# Adafruit_NeoMatrix_8x8.net
KiCad netlist of a schematic drawn in EAGLE
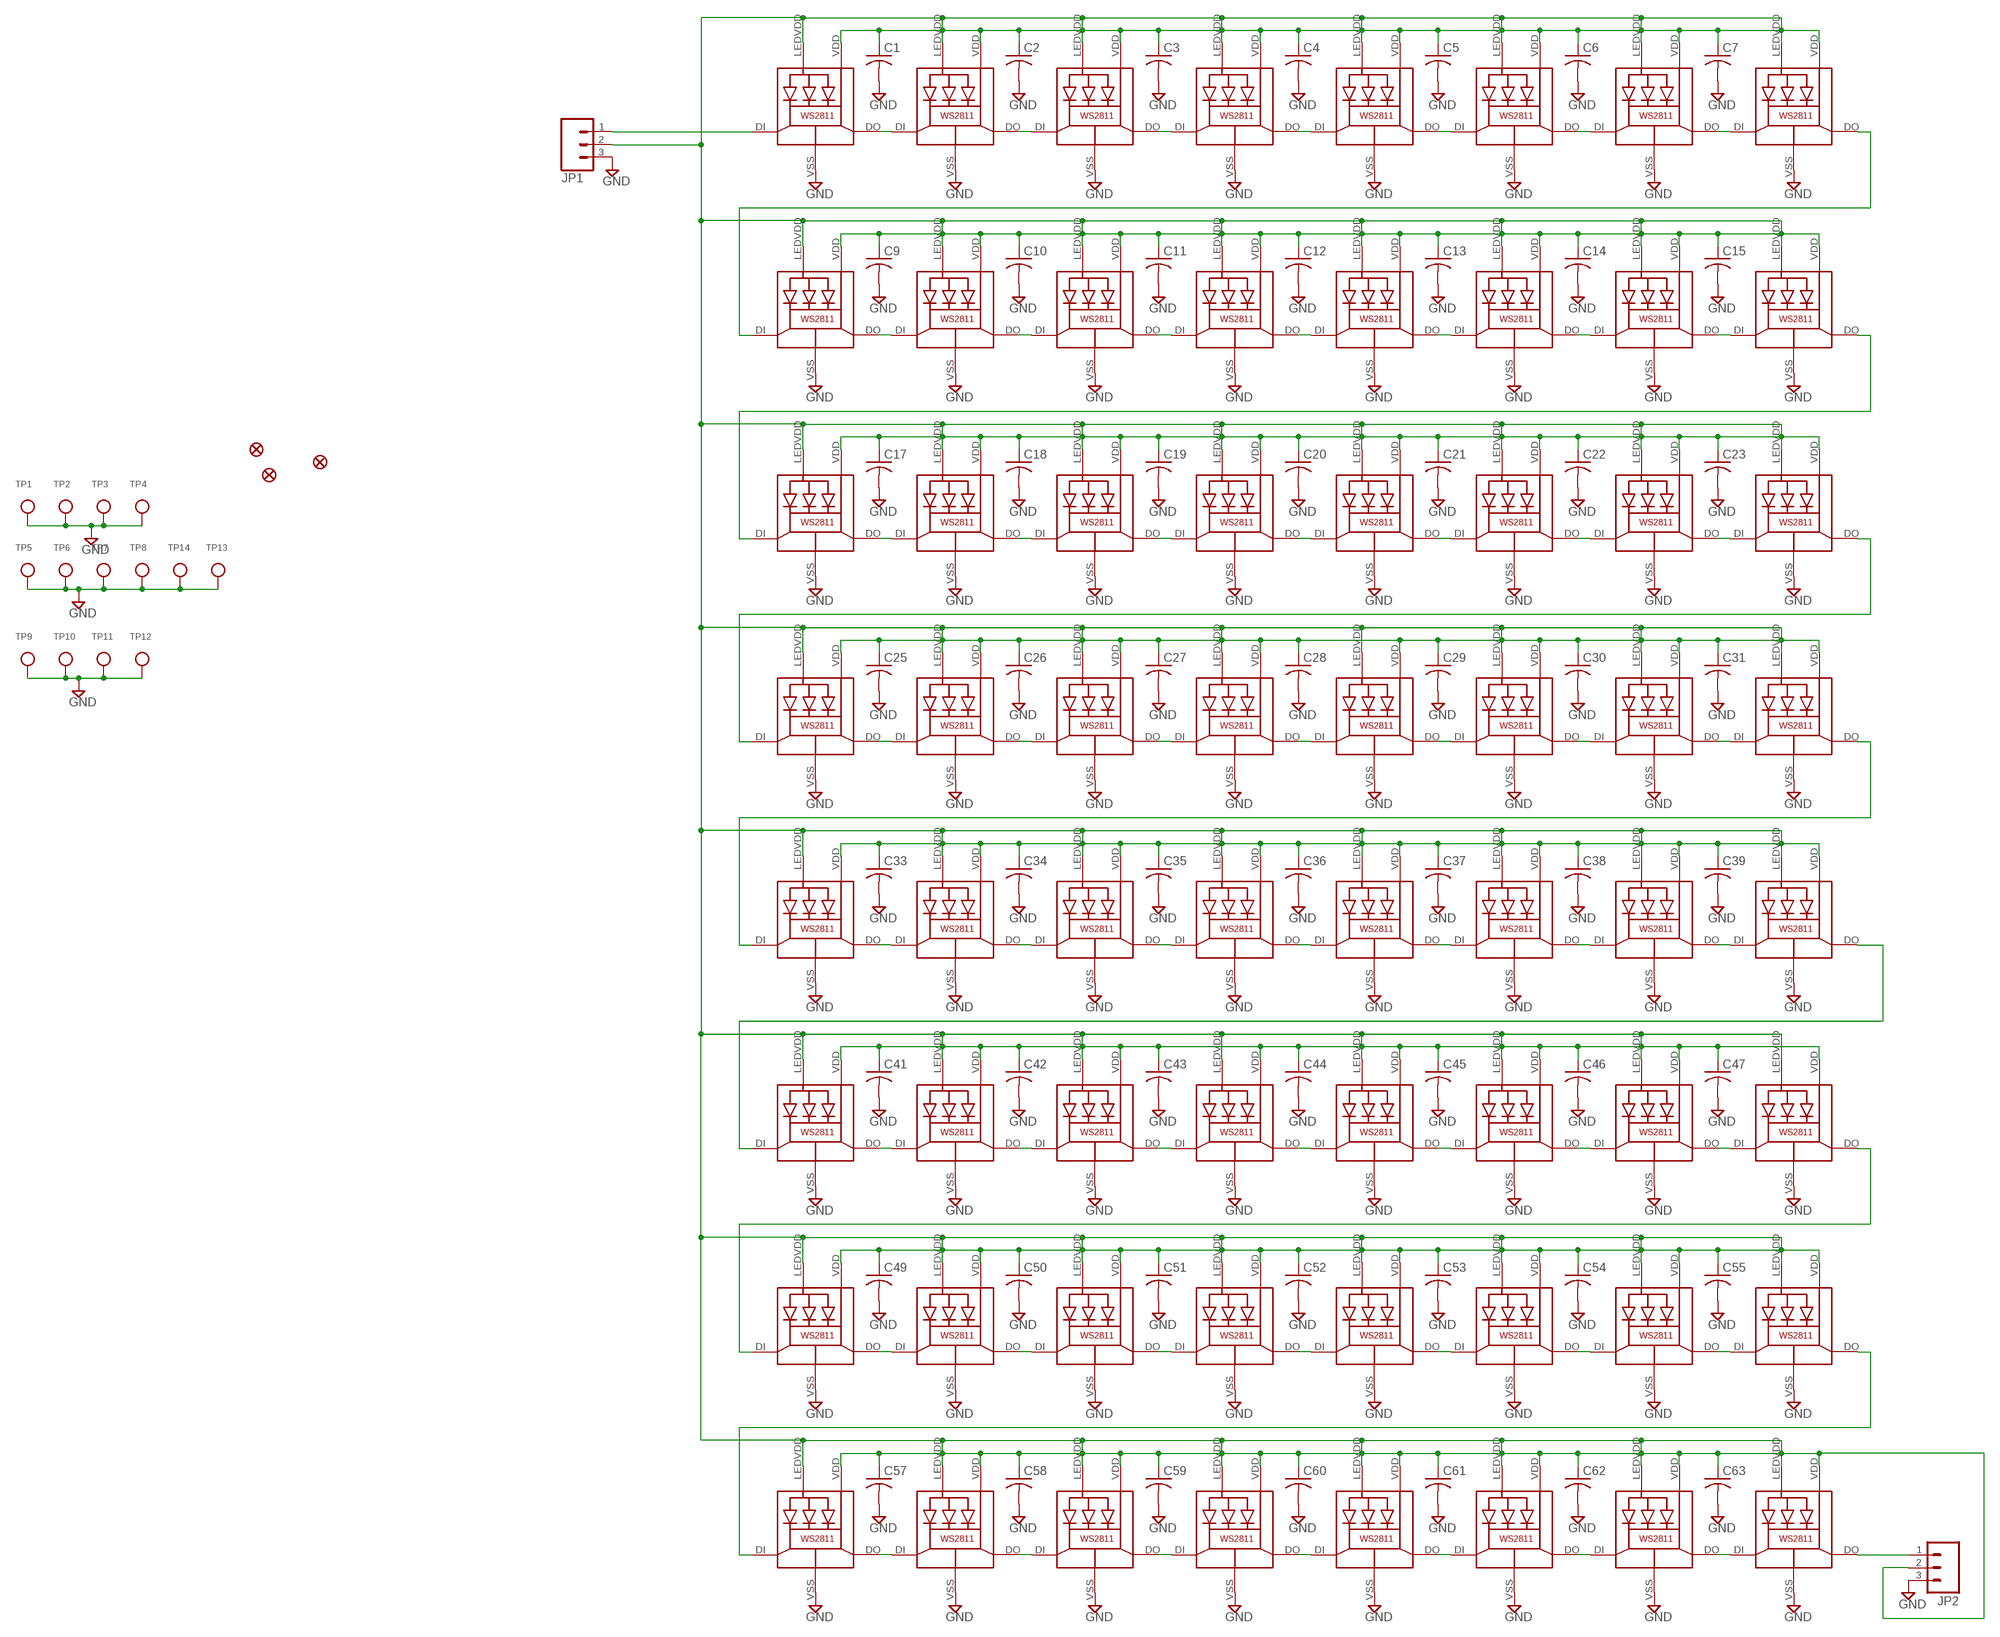
[diagram p0: schematic, sheet 1]

(export (version "E")
  (design (tool "Eeschema 10.0.6"))
  (components
    (comp (ref "C1")
      (value "RCL_C-USC0805K")
      (footprint "eagle-import:RCL_C0805K")
      (libsource (lib "eagle-import") (part "RCL_C-USC0805K"))
    )
    (comp (ref "C2")
      (value "RCL_C-USC0805K")
      (footprint "eagle-import:RCL_C0805K")
      (libsource (lib "eagle-import") (part "RCL_C-USC0805K"))
    )
    (comp (ref "C3")
      (value "RCL_C-USC0805K")
      (footprint "eagle-import:RCL_C0805K")
      (libsource (lib "eagle-import") (part "RCL_C-USC0805K"))
    )
    (comp (ref "C4")
      (value "RCL_C-USC0805K")
      (footprint "eagle-import:RCL_C0805K")
      (libsource (lib "eagle-import") (part "RCL_C-USC0805K"))
    )
    (comp (ref "C5")
      (value "RCL_C-USC0805K")
      (footprint "eagle-import:RCL_C0805K")
      (libsource (lib "eagle-import") (part "RCL_C-USC0805K"))
    )
    (comp (ref "C6")
      (value "RCL_C-USC0805K")
      (footprint "eagle-import:RCL_C0805K")
      (libsource (lib "eagle-import") (part "RCL_C-USC0805K"))
    )
    (comp (ref "C7")
      (value "RCL_C-USC0805K")
      (footprint "eagle-import:RCL_C0805K")
      (libsource (lib "eagle-import") (part "RCL_C-USC0805K"))
    )
    (comp (ref "C9")
      (value "RCL_C-USC0805K")
      (footprint "eagle-import:RCL_C0805K")
      (libsource (lib "eagle-import") (part "RCL_C-USC0805K"))
    )
    (comp (ref "C10")
      (value "RCL_C-USC0805K")
      (footprint "eagle-import:RCL_C0805K")
      (libsource (lib "eagle-import") (part "RCL_C-USC0805K"))
    )
    (comp (ref "C11")
      (value "RCL_C-USC0805K")
      (footprint "eagle-import:RCL_C0805K")
      (libsource (lib "eagle-import") (part "RCL_C-USC0805K"))
    )
    (comp (ref "C12")
      (value "RCL_C-USC0805K")
      (footprint "eagle-import:RCL_C0805K")
      (libsource (lib "eagle-import") (part "RCL_C-USC0805K"))
    )
    (comp (ref "C13")
      (value "RCL_C-USC0805K")
      (footprint "eagle-import:RCL_C0805K")
      (libsource (lib "eagle-import") (part "RCL_C-USC0805K"))
    )
    (comp (ref "C14")
      (value "RCL_C-USC0805K")
      (footprint "eagle-import:RCL_C0805K")
      (libsource (lib "eagle-import") (part "RCL_C-USC0805K"))
    )
    (comp (ref "C15")
      (value "RCL_C-USC0805K")
      (footprint "eagle-import:RCL_C0805K")
      (libsource (lib "eagle-import") (part "RCL_C-USC0805K"))
    )
    (comp (ref "C17")
      (value "RCL_C-USC0805K")
      (footprint "eagle-import:RCL_C0805K")
      (libsource (lib "eagle-import") (part "RCL_C-USC0805K"))
    )
    (comp (ref "C18")
      (value "RCL_C-USC0805K")
      (footprint "eagle-import:RCL_C0805K")
      (libsource (lib "eagle-import") (part "RCL_C-USC0805K"))
    )
    (comp (ref "C19")
      (value "RCL_C-USC0805K")
      (footprint "eagle-import:RCL_C0805K")
      (libsource (lib "eagle-import") (part "RCL_C-USC0805K"))
    )
    (comp (ref "C20")
      (value "RCL_C-USC0805K")
      (footprint "eagle-import:RCL_C0805K")
      (libsource (lib "eagle-import") (part "RCL_C-USC0805K"))
    )
    (comp (ref "C21")
      (value "RCL_C-USC0805K")
      (footprint "eagle-import:RCL_C0805K")
      (libsource (lib "eagle-import") (part "RCL_C-USC0805K"))
    )
    (comp (ref "C22")
      (value "RCL_C-USC0805K")
      (footprint "eagle-import:RCL_C0805K")
      (libsource (lib "eagle-import") (part "RCL_C-USC0805K"))
    )
    (comp (ref "C23")
      (value "RCL_C-USC0805K")
      (footprint "eagle-import:RCL_C0805K")
      (libsource (lib "eagle-import") (part "RCL_C-USC0805K"))
    )
    (comp (ref "C25")
      (value "RCL_C-USC0805K")
      (footprint "eagle-import:RCL_C0805K")
      (libsource (lib "eagle-import") (part "RCL_C-USC0805K"))
    )
    (comp (ref "C26")
      (value "RCL_C-USC0805K")
      (footprint "eagle-import:RCL_C0805K")
      (libsource (lib "eagle-import") (part "RCL_C-USC0805K"))
    )
    (comp (ref "C27")
      (value "RCL_C-USC0805K")
      (footprint "eagle-import:RCL_C0805K")
      (libsource (lib "eagle-import") (part "RCL_C-USC0805K"))
    )
    (comp (ref "C28")
      (value "RCL_C-USC0805K")
      (footprint "eagle-import:RCL_C0805K")
      (libsource (lib "eagle-import") (part "RCL_C-USC0805K"))
    )
    (comp (ref "C29")
      (value "RCL_C-USC0805K")
      (footprint "eagle-import:RCL_C0805K")
      (libsource (lib "eagle-import") (part "RCL_C-USC0805K"))
    )
    (comp (ref "C30")
      (value "RCL_C-USC0805K")
      (footprint "eagle-import:RCL_C0805K")
      (libsource (lib "eagle-import") (part "RCL_C-USC0805K"))
    )
    (comp (ref "C31")
      (value "RCL_C-USC0805K")
      (footprint "eagle-import:RCL_C0805K")
      (libsource (lib "eagle-import") (part "RCL_C-USC0805K"))
    )
    (comp (ref "C33")
      (value "RCL_C-USC0805K")
      (footprint "eagle-import:RCL_C0805K")
      (libsource (lib "eagle-import") (part "RCL_C-USC0805K"))
    )
    (comp (ref "C34")
      (value "RCL_C-USC0805K")
      (footprint "eagle-import:RCL_C0805K")
      (libsource (lib "eagle-import") (part "RCL_C-USC0805K"))
    )
    (comp (ref "C35")
      (value "RCL_C-USC0805K")
      (footprint "eagle-import:RCL_C0805K")
      (libsource (lib "eagle-import") (part "RCL_C-USC0805K"))
    )
    (comp (ref "C36")
      (value "RCL_C-USC0805K")
      (footprint "eagle-import:RCL_C0805K")
      (libsource (lib "eagle-import") (part "RCL_C-USC0805K"))
    )
    (comp (ref "C37")
      (value "RCL_C-USC0805K")
      (footprint "eagle-import:RCL_C0805K")
      (libsource (lib "eagle-import") (part "RCL_C-USC0805K"))
    )
    (comp (ref "C38")
      (value "RCL_C-USC0805K")
      (footprint "eagle-import:RCL_C0805K")
      (libsource (lib "eagle-import") (part "RCL_C-USC0805K"))
    )
    (comp (ref "C39")
      (value "RCL_C-USC0805K")
      (footprint "eagle-import:RCL_C0805K")
      (libsource (lib "eagle-import") (part "RCL_C-USC0805K"))
    )
    (comp (ref "C41")
      (value "RCL_C-USC0805K")
      (footprint "eagle-import:RCL_C0805K")
      (libsource (lib "eagle-import") (part "RCL_C-USC0805K"))
    )
    (comp (ref "C42")
      (value "RCL_C-USC0805K")
      (footprint "eagle-import:RCL_C0805K")
      (libsource (lib "eagle-import") (part "RCL_C-USC0805K"))
    )
    (comp (ref "C43")
      (value "RCL_C-USC0805K")
      (footprint "eagle-import:RCL_C0805K")
      (libsource (lib "eagle-import") (part "RCL_C-USC0805K"))
    )
    (comp (ref "C44")
      (value "RCL_C-USC0805K")
      (footprint "eagle-import:RCL_C0805K")
      (libsource (lib "eagle-import") (part "RCL_C-USC0805K"))
    )
    (comp (ref "C45")
      (value "RCL_C-USC0805K")
      (footprint "eagle-import:RCL_C0805K")
      (libsource (lib "eagle-import") (part "RCL_C-USC0805K"))
    )
    (comp (ref "C46")
      (value "RCL_C-USC0805K")
      (footprint "eagle-import:RCL_C0805K")
      (libsource (lib "eagle-import") (part "RCL_C-USC0805K"))
    )
    (comp (ref "C47")
      (value "RCL_C-USC0805K")
      (footprint "eagle-import:RCL_C0805K")
      (libsource (lib "eagle-import") (part "RCL_C-USC0805K"))
    )
    (comp (ref "C49")
      (value "RCL_C-USC0805K")
      (footprint "eagle-import:RCL_C0805K")
      (libsource (lib "eagle-import") (part "RCL_C-USC0805K"))
    )
    (comp (ref "C50")
      (value "RCL_C-USC0805K")
      (footprint "eagle-import:RCL_C0805K")
      (libsource (lib "eagle-import") (part "RCL_C-USC0805K"))
    )
    (comp (ref "C51")
      (value "RCL_C-USC0805K")
      (footprint "eagle-import:RCL_C0805K")
      (libsource (lib "eagle-import") (part "RCL_C-USC0805K"))
    )
    (comp (ref "C52")
      (value "RCL_C-USC0805K")
      (footprint "eagle-import:RCL_C0805K")
      (libsource (lib "eagle-import") (part "RCL_C-USC0805K"))
    )
    (comp (ref "C53")
      (value "RCL_C-USC0805K")
      (footprint "eagle-import:RCL_C0805K")
      (libsource (lib "eagle-import") (part "RCL_C-USC0805K"))
    )
    (comp (ref "C54")
      (value "RCL_C-USC0805K")
      (footprint "eagle-import:RCL_C0805K")
      (libsource (lib "eagle-import") (part "RCL_C-USC0805K"))
    )
    (comp (ref "C55")
      (value "RCL_C-USC0805K")
      (footprint "eagle-import:RCL_C0805K")
      (libsource (lib "eagle-import") (part "RCL_C-USC0805K"))
    )
    (comp (ref "C57")
      (value "RCL_C-USC0805K")
      (footprint "eagle-import:RCL_C0805K")
      (libsource (lib "eagle-import") (part "RCL_C-USC0805K"))
    )
    (comp (ref "C58")
      (value "RCL_C-USC0805K")
      (footprint "eagle-import:RCL_C0805K")
      (libsource (lib "eagle-import") (part "RCL_C-USC0805K"))
    )
    (comp (ref "C59")
      (value "RCL_C-USC0805K")
      (footprint "eagle-import:RCL_C0805K")
      (libsource (lib "eagle-import") (part "RCL_C-USC0805K"))
    )
    (comp (ref "C60")
      (value "RCL_C-USC0805K")
      (footprint "eagle-import:RCL_C0805K")
      (libsource (lib "eagle-import") (part "RCL_C-USC0805K"))
    )
    (comp (ref "C61")
      (value "RCL_C-USC0805K")
      (footprint "eagle-import:RCL_C0805K")
      (libsource (lib "eagle-import") (part "RCL_C-USC0805K"))
    )
    (comp (ref "C62")
      (value "RCL_C-USC0805K")
      (footprint "eagle-import:RCL_C0805K")
      (libsource (lib "eagle-import") (part "RCL_C-USC0805K"))
    )
    (comp (ref "C63")
      (value "RCL_C-USC0805K")
      (footprint "eagle-import:RCL_C0805K")
      (libsource (lib "eagle-import") (part "RCL_C-USC0805K"))
    )
    (comp (ref "FID1")
      (value "FIDUCIAL\"\"")
      (footprint "eagle-import:FIDUCIAL_1MM")
      (libsource (lib "eagle-import") (part "FIDUCIAL{dblquote}{dblquote}"))
    )
    (comp (ref "FID2")
      (value "FIDUCIAL\"\"")
      (footprint "eagle-import:FIDUCIAL_1MM")
      (libsource (lib "eagle-import") (part "FIDUCIAL{dblquote}{dblquote}"))
    )
    (comp (ref "FID3")
      (value "FIDUCIAL\"\"")
      (footprint "eagle-import:FIDUCIAL_1MM")
      (libsource (lib "eagle-import") (part "FIDUCIAL{dblquote}{dblquote}"))
    )
    (comp (ref "JP1")
      (value "M03PTH")
      (footprint "eagle-import:1X03")
      (libsource (lib "eagle-import") (part "M03PTH"))
    )
    (comp (ref "JP2")
      (value "M03PTH")
      (footprint "eagle-import:1X03")
      (libsource (lib "eagle-import") (part "M03PTH"))
    )
    (comp (ref "LED1")
      (value "WS28115050")
      (footprint "eagle-import:WS28115050")
      (libsource (lib "eagle-import") (part "WS28115050"))
    )
    (comp (ref "LED2")
      (value "WS28115050")
      (footprint "eagle-import:WS28115050")
      (libsource (lib "eagle-import") (part "WS28115050"))
    )
    (comp (ref "LED3")
      (value "WS28115050")
      (footprint "eagle-import:WS28115050")
      (libsource (lib "eagle-import") (part "WS28115050"))
    )
    (comp (ref "LED4")
      (value "WS28115050")
      (footprint "eagle-import:WS28115050")
      (libsource (lib "eagle-import") (part "WS28115050"))
    )
    (comp (ref "LED5")
      (value "WS28115050")
      (footprint "eagle-import:WS28115050")
      (libsource (lib "eagle-import") (part "WS28115050"))
    )
    (comp (ref "LED6")
      (value "WS28115050")
      (footprint "eagle-import:WS28115050")
      (libsource (lib "eagle-import") (part "WS28115050"))
    )
    (comp (ref "LED7")
      (value "WS28115050")
      (footprint "eagle-import:WS28115050")
      (libsource (lib "eagle-import") (part "WS28115050"))
    )
    (comp (ref "LED8")
      (value "WS28115050")
      (footprint "eagle-import:WS28115050")
      (libsource (lib "eagle-import") (part "WS28115050"))
    )
    (comp (ref "LED9")
      (value "WS28115050")
      (footprint "eagle-import:WS28115050")
      (libsource (lib "eagle-import") (part "WS28115050"))
    )
    (comp (ref "LED10")
      (value "WS28115050")
      (footprint "eagle-import:WS28115050")
      (libsource (lib "eagle-import") (part "WS28115050"))
    )
    (comp (ref "LED11")
      (value "WS28115050")
      (footprint "eagle-import:WS28115050")
      (libsource (lib "eagle-import") (part "WS28115050"))
    )
    (comp (ref "LED12")
      (value "WS28115050")
      (footprint "eagle-import:WS28115050")
      (libsource (lib "eagle-import") (part "WS28115050"))
    )
    (comp (ref "LED13")
      (value "WS28115050")
      (footprint "eagle-import:WS28115050")
      (libsource (lib "eagle-import") (part "WS28115050"))
    )
    (comp (ref "LED14")
      (value "WS28115050")
      (footprint "eagle-import:WS28115050")
      (libsource (lib "eagle-import") (part "WS28115050"))
    )
    (comp (ref "LED15")
      (value "WS28115050")
      (footprint "eagle-import:WS28115050")
      (libsource (lib "eagle-import") (part "WS28115050"))
    )
    (comp (ref "LED16")
      (value "WS28115050")
      (footprint "eagle-import:WS28115050")
      (libsource (lib "eagle-import") (part "WS28115050"))
    )
    (comp (ref "LED17")
      (value "WS28115050")
      (footprint "eagle-import:WS28115050")
      (libsource (lib "eagle-import") (part "WS28115050"))
    )
    (comp (ref "LED18")
      (value "WS28115050")
      (footprint "eagle-import:WS28115050")
      (libsource (lib "eagle-import") (part "WS28115050"))
    )
    (comp (ref "LED19")
      (value "WS28115050")
      (footprint "eagle-import:WS28115050")
      (libsource (lib "eagle-import") (part "WS28115050"))
    )
    (comp (ref "LED20")
      (value "WS28115050")
      (footprint "eagle-import:WS28115050")
      (libsource (lib "eagle-import") (part "WS28115050"))
    )
    (comp (ref "LED21")
      (value "WS28115050")
      (footprint "eagle-import:WS28115050")
      (libsource (lib "eagle-import") (part "WS28115050"))
    )
    (comp (ref "LED22")
      (value "WS28115050")
      (footprint "eagle-import:WS28115050")
      (libsource (lib "eagle-import") (part "WS28115050"))
    )
    (comp (ref "LED23")
      (value "WS28115050")
      (footprint "eagle-import:WS28115050")
      (libsource (lib "eagle-import") (part "WS28115050"))
    )
    (comp (ref "LED24")
      (value "WS28115050")
      (footprint "eagle-import:WS28115050")
      (libsource (lib "eagle-import") (part "WS28115050"))
    )
    (comp (ref "LED25")
      (value "WS28115050")
      (footprint "eagle-import:WS28115050")
      (libsource (lib "eagle-import") (part "WS28115050"))
    )
    (comp (ref "LED26")
      (value "WS28115050")
      (footprint "eagle-import:WS28115050")
      (libsource (lib "eagle-import") (part "WS28115050"))
    )
    (comp (ref "LED27")
      (value "WS28115050")
      (footprint "eagle-import:WS28115050")
      (libsource (lib "eagle-import") (part "WS28115050"))
    )
    (comp (ref "LED28")
      (value "WS28115050")
      (footprint "eagle-import:WS28115050")
      (libsource (lib "eagle-import") (part "WS28115050"))
    )
    (comp (ref "LED29")
      (value "WS28115050")
      (footprint "eagle-import:WS28115050")
      (libsource (lib "eagle-import") (part "WS28115050"))
    )
    (comp (ref "LED30")
      (value "WS28115050")
      (footprint "eagle-import:WS28115050")
      (libsource (lib "eagle-import") (part "WS28115050"))
    )
    (comp (ref "LED31")
      (value "WS28115050")
      (footprint "eagle-import:WS28115050")
      (libsource (lib "eagle-import") (part "WS28115050"))
    )
    (comp (ref "LED32")
      (value "WS28115050")
      (footprint "eagle-import:WS28115050")
      (libsource (lib "eagle-import") (part "WS28115050"))
    )
    (comp (ref "LED33")
      (value "WS28115050")
      (footprint "eagle-import:WS28115050")
      (libsource (lib "eagle-import") (part "WS28115050"))
    )
    (comp (ref "LED34")
      (value "WS28115050")
      (footprint "eagle-import:WS28115050")
      (libsource (lib "eagle-import") (part "WS28115050"))
    )
    (comp (ref "LED35")
      (value "WS28115050")
      (footprint "eagle-import:WS28115050")
      (libsource (lib "eagle-import") (part "WS28115050"))
    )
    (comp (ref "LED36")
      (value "WS28115050")
      (footprint "eagle-import:WS28115050")
      (libsource (lib "eagle-import") (part "WS28115050"))
    )
    (comp (ref "LED37")
      (value "WS28115050")
      (footprint "eagle-import:WS28115050")
      (libsource (lib "eagle-import") (part "WS28115050"))
    )
    (comp (ref "LED38")
      (value "WS28115050")
      (footprint "eagle-import:WS28115050")
      (libsource (lib "eagle-import") (part "WS28115050"))
    )
    (comp (ref "LED39")
      (value "WS28115050")
      (footprint "eagle-import:WS28115050")
      (libsource (lib "eagle-import") (part "WS28115050"))
    )
    (comp (ref "LED40")
      (value "WS28115050")
      (footprint "eagle-import:WS28115050")
      (libsource (lib "eagle-import") (part "WS28115050"))
    )
    (comp (ref "LED41")
      (value "WS28115050")
      (footprint "eagle-import:WS28115050")
      (libsource (lib "eagle-import") (part "WS28115050"))
    )
    (comp (ref "LED42")
      (value "WS28115050")
      (footprint "eagle-import:WS28115050")
      (libsource (lib "eagle-import") (part "WS28115050"))
    )
    (comp (ref "LED43")
      (value "WS28115050")
      (footprint "eagle-import:WS28115050")
      (libsource (lib "eagle-import") (part "WS28115050"))
    )
    (comp (ref "LED44")
      (value "WS28115050")
      (footprint "eagle-import:WS28115050")
      (libsource (lib "eagle-import") (part "WS28115050"))
    )
    (comp (ref "LED45")
      (value "WS28115050")
      (footprint "eagle-import:WS28115050")
      (libsource (lib "eagle-import") (part "WS28115050"))
    )
    (comp (ref "LED46")
      (value "WS28115050")
      (footprint "eagle-import:WS28115050")
      (libsource (lib "eagle-import") (part "WS28115050"))
    )
    (comp (ref "LED47")
      (value "WS28115050")
      (footprint "eagle-import:WS28115050")
      (libsource (lib "eagle-import") (part "WS28115050"))
    )
    (comp (ref "LED48")
      (value "WS28115050")
      (footprint "eagle-import:WS28115050")
      (libsource (lib "eagle-import") (part "WS28115050"))
    )
    (comp (ref "LED49")
      (value "WS28115050")
      (footprint "eagle-import:WS28115050")
      (libsource (lib "eagle-import") (part "WS28115050"))
    )
    (comp (ref "LED50")
      (value "WS28115050")
      (footprint "eagle-import:WS28115050")
      (libsource (lib "eagle-import") (part "WS28115050"))
    )
    (comp (ref "LED51")
      (value "WS28115050")
      (footprint "eagle-import:WS28115050")
      (libsource (lib "eagle-import") (part "WS28115050"))
    )
    (comp (ref "LED52")
      (value "WS28115050")
      (footprint "eagle-import:WS28115050")
      (libsource (lib "eagle-import") (part "WS28115050"))
    )
    (comp (ref "LED53")
      (value "WS28115050")
      (footprint "eagle-import:WS28115050")
      (libsource (lib "eagle-import") (part "WS28115050"))
    )
    (comp (ref "LED54")
      (value "WS28115050")
      (footprint "eagle-import:WS28115050")
      (libsource (lib "eagle-import") (part "WS28115050"))
    )
    (comp (ref "LED55")
      (value "WS28115050")
      (footprint "eagle-import:WS28115050")
      (libsource (lib "eagle-import") (part "WS28115050"))
    )
    (comp (ref "LED56")
      (value "WS28115050")
      (footprint "eagle-import:WS28115050")
      (libsource (lib "eagle-import") (part "WS28115050"))
    )
    (comp (ref "LED57")
      (value "WS28115050")
      (footprint "eagle-import:WS28115050")
      (libsource (lib "eagle-import") (part "WS28115050"))
    )
    (comp (ref "LED58")
      (value "WS28115050")
      (footprint "eagle-import:WS28115050")
      (libsource (lib "eagle-import") (part "WS28115050"))
    )
    (comp (ref "LED59")
      (value "WS28115050")
      (footprint "eagle-import:WS28115050")
      (libsource (lib "eagle-import") (part "WS28115050"))
    )
    (comp (ref "LED60")
      (value "WS28115050")
      (footprint "eagle-import:WS28115050")
      (libsource (lib "eagle-import") (part "WS28115050"))
    )
    (comp (ref "LED61")
      (value "WS28115050")
      (footprint "eagle-import:WS28115050")
      (libsource (lib "eagle-import") (part "WS28115050"))
    )
    (comp (ref "LED62")
      (value "WS28115050")
      (footprint "eagle-import:WS28115050")
      (libsource (lib "eagle-import") (part "WS28115050"))
    )
    (comp (ref "LED63")
      (value "WS28115050")
      (footprint "eagle-import:WS28115050")
      (libsource (lib "eagle-import") (part "WS28115050"))
    )
    (comp (ref "LED64")
      (value "WS28115050")
      (footprint "eagle-import:WS28115050")
      (libsource (lib "eagle-import") (part "WS28115050"))
    )
    (comp (ref "TP1")
      (value "TESTPOINT")
      (footprint "eagle-import:TESTPOINT_SMT")
      (libsource (lib "eagle-import") (part "TESTPOINT"))
    )
    (comp (ref "TP2")
      (value "TESTPOINT")
      (footprint "eagle-import:TESTPOINT_SMT")
      (libsource (lib "eagle-import") (part "TESTPOINT"))
    )
    (comp (ref "TP3")
      (value "TESTPOINT")
      (footprint "eagle-import:TESTPOINT_SMT")
      (libsource (lib "eagle-import") (part "TESTPOINT"))
    )
    (comp (ref "TP4")
      (value "TESTPOINT")
      (footprint "eagle-import:TESTPOINT_SMT")
      (libsource (lib "eagle-import") (part "TESTPOINT"))
    )
    (comp (ref "TP5")
      (value "TESTPOINT")
      (footprint "eagle-import:TESTPOINT_SMT")
      (libsource (lib "eagle-import") (part "TESTPOINT"))
    )
    (comp (ref "TP6")
      (value "TESTPOINT")
      (footprint "eagle-import:TESTPOINT_SMT")
      (libsource (lib "eagle-import") (part "TESTPOINT"))
    )
    (comp (ref "TP7")
      (value "TESTPOINT")
      (footprint "eagle-import:TESTPOINT_SMT")
      (libsource (lib "eagle-import") (part "TESTPOINT"))
    )
    (comp (ref "TP8")
      (value "TESTPOINT")
      (footprint "eagle-import:TESTPOINT_SMT")
      (libsource (lib "eagle-import") (part "TESTPOINT"))
    )
    (comp (ref "TP9")
      (value "TESTPOINT")
      (footprint "eagle-import:TESTPOINT_SMT")
      (libsource (lib "eagle-import") (part "TESTPOINT"))
    )
    (comp (ref "TP10")
      (value "TESTPOINT")
      (footprint "eagle-import:TESTPOINT_SMT")
      (libsource (lib "eagle-import") (part "TESTPOINT"))
    )
    (comp (ref "TP11")
      (value "TESTPOINT")
      (footprint "eagle-import:TESTPOINT_SMT")
      (libsource (lib "eagle-import") (part "TESTPOINT"))
    )
    (comp (ref "TP12")
      (value "TESTPOINT")
      (footprint "eagle-import:TESTPOINT_SMT")
      (libsource (lib "eagle-import") (part "TESTPOINT"))
    )
    (comp (ref "TP13")
      (value "TESTPOINT")
      (footprint "eagle-import:TESTPOINT_SMT")
      (libsource (lib "eagle-import") (part "TESTPOINT"))
    )
    (comp (ref "TP14")
      (value "TESTPOINT")
      (footprint "eagle-import:TESTPOINT_SMT")
      (libsource (lib "eagle-import") (part "TESTPOINT"))
    )
  )
  (nets
    (net (code "1") (name "GND") (class "Default")
      (node (ref "C1") (pin "2") (pinfunction "2_2") (pintype "passive"))
      (node (ref "C10") (pin "2") (pinfunction "2_2") (pintype "passive"))
      (node (ref "C11") (pin "2") (pinfunction "2_2") (pintype "passive"))
      (node (ref "C12") (pin "2") (pinfunction "2_2") (pintype "passive"))
      (node (ref "C13") (pin "2") (pinfunction "2_2") (pintype "passive"))
      (node (ref "C14") (pin "2") (pinfunction "2_2") (pintype "passive"))
      (node (ref "C15") (pin "2") (pinfunction "2_2") (pintype "passive"))
      (node (ref "C17") (pin "2") (pinfunction "2_2") (pintype "passive"))
      (node (ref "C18") (pin "2") (pinfunction "2_2") (pintype "passive"))
      (node (ref "C19") (pin "2") (pinfunction "2_2") (pintype "passive"))
      (node (ref "C2") (pin "2") (pinfunction "2_2") (pintype "passive"))
      (node (ref "C20") (pin "2") (pinfunction "2_2") (pintype "passive"))
      (node (ref "C21") (pin "2") (pinfunction "2_2") (pintype "passive"))
      (node (ref "C22") (pin "2") (pinfunction "2_2") (pintype "passive"))
      (node (ref "C23") (pin "2") (pinfunction "2_2") (pintype "passive"))
      (node (ref "C25") (pin "2") (pinfunction "2_2") (pintype "passive"))
      (node (ref "C26") (pin "2") (pinfunction "2_2") (pintype "passive"))
      (node (ref "C27") (pin "2") (pinfunction "2_2") (pintype "passive"))
      (node (ref "C28") (pin "2") (pinfunction "2_2") (pintype "passive"))
      (node (ref "C29") (pin "2") (pinfunction "2_2") (pintype "passive"))
      (node (ref "C3") (pin "2") (pinfunction "2_2") (pintype "passive"))
      (node (ref "C30") (pin "2") (pinfunction "2_2") (pintype "passive"))
      (node (ref "C31") (pin "2") (pinfunction "2_2") (pintype "passive"))
      (node (ref "C33") (pin "2") (pinfunction "2_2") (pintype "passive"))
      (node (ref "C34") (pin "2") (pinfunction "2_2") (pintype "passive"))
      (node (ref "C35") (pin "2") (pinfunction "2_2") (pintype "passive"))
      (node (ref "C36") (pin "2") (pinfunction "2_2") (pintype "passive"))
      (node (ref "C37") (pin "2") (pinfunction "2_2") (pintype "passive"))
      (node (ref "C38") (pin "2") (pinfunction "2_2") (pintype "passive"))
      (node (ref "C39") (pin "2") (pinfunction "2_2") (pintype "passive"))
      (node (ref "C4") (pin "2") (pinfunction "2_2") (pintype "passive"))
      (node (ref "C41") (pin "2") (pinfunction "2_2") (pintype "passive"))
      (node (ref "C42") (pin "2") (pinfunction "2_2") (pintype "passive"))
      (node (ref "C43") (pin "2") (pinfunction "2_2") (pintype "passive"))
      (node (ref "C44") (pin "2") (pinfunction "2_2") (pintype "passive"))
      (node (ref "C45") (pin "2") (pinfunction "2_2") (pintype "passive"))
      (node (ref "C46") (pin "2") (pinfunction "2_2") (pintype "passive"))
      (node (ref "C47") (pin "2") (pinfunction "2_2") (pintype "passive"))
      (node (ref "C49") (pin "2") (pinfunction "2_2") (pintype "passive"))
      (node (ref "C5") (pin "2") (pinfunction "2_2") (pintype "passive"))
      (node (ref "C50") (pin "2") (pinfunction "2_2") (pintype "passive"))
      (node (ref "C51") (pin "2") (pinfunction "2_2") (pintype "passive"))
      (node (ref "C52") (pin "2") (pinfunction "2_2") (pintype "passive"))
      (node (ref "C53") (pin "2") (pinfunction "2_2") (pintype "passive"))
      (node (ref "C54") (pin "2") (pinfunction "2_2") (pintype "passive"))
      (node (ref "C55") (pin "2") (pinfunction "2_2") (pintype "passive"))
      (node (ref "C57") (pin "2") (pinfunction "2_2") (pintype "passive"))
      (node (ref "C58") (pin "2") (pinfunction "2_2") (pintype "passive"))
      (node (ref "C59") (pin "2") (pinfunction "2_2") (pintype "passive"))
      (node (ref "C6") (pin "2") (pinfunction "2_2") (pintype "passive"))
      (node (ref "C60") (pin "2") (pinfunction "2_2") (pintype "passive"))
      (node (ref "C61") (pin "2") (pinfunction "2_2") (pintype "passive"))
      (node (ref "C62") (pin "2") (pinfunction "2_2") (pintype "passive"))
      (node (ref "C63") (pin "2") (pinfunction "2_2") (pintype "passive"))
      (node (ref "C7") (pin "2") (pinfunction "2_2") (pintype "passive"))
      (node (ref "C9") (pin "2") (pinfunction "2_2") (pintype "passive"))
      (node (ref "JP1") (pin "3") (pinfunction "3_3") (pintype "passive"))
      (node (ref "JP2") (pin "3") (pinfunction "3_3") (pintype "passive"))
      (node (ref "LED1") (pin "VSS") (pinfunction "GND_VSS") (pintype "power_in"))
      (node (ref "LED10") (pin "VSS") (pinfunction "GND_VSS") (pintype "power_in"))
      (node (ref "LED11") (pin "VSS") (pinfunction "GND_VSS") (pintype "power_in"))
      (node (ref "LED12") (pin "VSS") (pinfunction "GND_VSS") (pintype "power_in"))
      (node (ref "LED13") (pin "VSS") (pinfunction "GND_VSS") (pintype "power_in"))
      (node (ref "LED14") (pin "VSS") (pinfunction "GND_VSS") (pintype "power_in"))
      (node (ref "LED15") (pin "VSS") (pinfunction "GND_VSS") (pintype "power_in"))
      (node (ref "LED16") (pin "VSS") (pinfunction "GND_VSS") (pintype "power_in"))
      (node (ref "LED17") (pin "VSS") (pinfunction "GND_VSS") (pintype "power_in"))
      (node (ref "LED18") (pin "VSS") (pinfunction "GND_VSS") (pintype "power_in"))
      (node (ref "LED19") (pin "VSS") (pinfunction "GND_VSS") (pintype "power_in"))
      (node (ref "LED2") (pin "VSS") (pinfunction "GND_VSS") (pintype "power_in"))
      (node (ref "LED20") (pin "VSS") (pinfunction "GND_VSS") (pintype "power_in"))
      (node (ref "LED21") (pin "VSS") (pinfunction "GND_VSS") (pintype "power_in"))
      (node (ref "LED22") (pin "VSS") (pinfunction "GND_VSS") (pintype "power_in"))
      (node (ref "LED23") (pin "VSS") (pinfunction "GND_VSS") (pintype "power_in"))
      (node (ref "LED24") (pin "VSS") (pinfunction "GND_VSS") (pintype "power_in"))
      (node (ref "LED25") (pin "VSS") (pinfunction "GND_VSS") (pintype "power_in"))
      (node (ref "LED26") (pin "VSS") (pinfunction "GND_VSS") (pintype "power_in"))
      (node (ref "LED27") (pin "VSS") (pinfunction "GND_VSS") (pintype "power_in"))
      (node (ref "LED28") (pin "VSS") (pinfunction "GND_VSS") (pintype "power_in"))
      (node (ref "LED29") (pin "VSS") (pinfunction "GND_VSS") (pintype "power_in"))
      (node (ref "LED3") (pin "VSS") (pinfunction "GND_VSS") (pintype "power_in"))
      (node (ref "LED30") (pin "VSS") (pinfunction "GND_VSS") (pintype "power_in"))
      (node (ref "LED31") (pin "VSS") (pinfunction "GND_VSS") (pintype "power_in"))
      (node (ref "LED32") (pin "VSS") (pinfunction "GND_VSS") (pintype "power_in"))
      (node (ref "LED33") (pin "VSS") (pinfunction "GND_VSS") (pintype "power_in"))
      (node (ref "LED34") (pin "VSS") (pinfunction "GND_VSS") (pintype "power_in"))
      (node (ref "LED35") (pin "VSS") (pinfunction "GND_VSS") (pintype "power_in"))
      (node (ref "LED36") (pin "VSS") (pinfunction "GND_VSS") (pintype "power_in"))
      (node (ref "LED37") (pin "VSS") (pinfunction "GND_VSS") (pintype "power_in"))
      (node (ref "LED38") (pin "VSS") (pinfunction "GND_VSS") (pintype "power_in"))
      (node (ref "LED39") (pin "VSS") (pinfunction "GND_VSS") (pintype "power_in"))
      (node (ref "LED4") (pin "VSS") (pinfunction "GND_VSS") (pintype "power_in"))
      (node (ref "LED40") (pin "VSS") (pinfunction "GND_VSS") (pintype "power_in"))
      (node (ref "LED41") (pin "VSS") (pinfunction "GND_VSS") (pintype "power_in"))
      (node (ref "LED42") (pin "VSS") (pinfunction "GND_VSS") (pintype "power_in"))
      (node (ref "LED43") (pin "VSS") (pinfunction "GND_VSS") (pintype "power_in"))
      (node (ref "LED44") (pin "VSS") (pinfunction "GND_VSS") (pintype "power_in"))
      (node (ref "LED45") (pin "VSS") (pinfunction "GND_VSS") (pintype "power_in"))
      (node (ref "LED46") (pin "VSS") (pinfunction "GND_VSS") (pintype "power_in"))
      (node (ref "LED47") (pin "VSS") (pinfunction "GND_VSS") (pintype "power_in"))
      (node (ref "LED48") (pin "VSS") (pinfunction "GND_VSS") (pintype "power_in"))
      (node (ref "LED49") (pin "VSS") (pinfunction "GND_VSS") (pintype "power_in"))
      (node (ref "LED5") (pin "VSS") (pinfunction "GND_VSS") (pintype "power_in"))
      (node (ref "LED50") (pin "VSS") (pinfunction "GND_VSS") (pintype "power_in"))
      (node (ref "LED51") (pin "VSS") (pinfunction "GND_VSS") (pintype "power_in"))
      (node (ref "LED52") (pin "VSS") (pinfunction "GND_VSS") (pintype "power_in"))
      (node (ref "LED53") (pin "VSS") (pinfunction "GND_VSS") (pintype "power_in"))
      (node (ref "LED54") (pin "VSS") (pinfunction "GND_VSS") (pintype "power_in"))
      (node (ref "LED55") (pin "VSS") (pinfunction "GND_VSS") (pintype "power_in"))
      (node (ref "LED56") (pin "VSS") (pinfunction "GND_VSS") (pintype "power_in"))
      (node (ref "LED57") (pin "VSS") (pinfunction "GND_VSS") (pintype "power_in"))
      (node (ref "LED58") (pin "VSS") (pinfunction "GND_VSS") (pintype "power_in"))
      (node (ref "LED59") (pin "VSS") (pinfunction "GND_VSS") (pintype "power_in"))
      (node (ref "LED6") (pin "VSS") (pinfunction "GND_VSS") (pintype "power_in"))
      (node (ref "LED60") (pin "VSS") (pinfunction "GND_VSS") (pintype "power_in"))
      (node (ref "LED61") (pin "VSS") (pinfunction "GND_VSS") (pintype "power_in"))
      (node (ref "LED62") (pin "VSS") (pinfunction "GND_VSS") (pintype "power_in"))
      (node (ref "LED63") (pin "VSS") (pinfunction "GND_VSS") (pintype "power_in"))
      (node (ref "LED64") (pin "VSS") (pinfunction "GND_VSS") (pintype "power_in"))
      (node (ref "LED7") (pin "VSS") (pinfunction "GND_VSS") (pintype "power_in"))
      (node (ref "LED8") (pin "VSS") (pinfunction "GND_VSS") (pintype "power_in"))
      (node (ref "LED9") (pin "VSS") (pinfunction "GND_VSS") (pintype "power_in"))
      (node (ref "TP1") (pin "P$1") (pinfunction "P$1_P$1") (pintype "bidirectional"))
      (node (ref "TP10") (pin "P$1") (pinfunction "P$1_P$1") (pintype "bidirectional"))
      (node (ref "TP11") (pin "P$1") (pinfunction "P$1_P$1") (pintype "bidirectional"))
      (node (ref "TP12") (pin "P$1") (pinfunction "P$1_P$1") (pintype "bidirectional"))
      (node (ref "TP13") (pin "P$1") (pinfunction "P$1_P$1") (pintype "bidirectional"))
      (node (ref "TP14") (pin "P$1") (pinfunction "P$1_P$1") (pintype "bidirectional"))
      (node (ref "TP2") (pin "P$1") (pinfunction "P$1_P$1") (pintype "bidirectional"))
      (node (ref "TP3") (pin "P$1") (pinfunction "P$1_P$1") (pintype "bidirectional"))
      (node (ref "TP4") (pin "P$1") (pinfunction "P$1_P$1") (pintype "bidirectional"))
      (node (ref "TP5") (pin "P$1") (pinfunction "P$1_P$1") (pintype "bidirectional"))
      (node (ref "TP6") (pin "P$1") (pinfunction "P$1_P$1") (pintype "bidirectional"))
      (node (ref "TP7") (pin "P$1") (pinfunction "P$1_P$1") (pintype "bidirectional"))
      (node (ref "TP8") (pin "P$1") (pinfunction "P$1_P$1") (pintype "bidirectional"))
      (node (ref "TP9") (pin "P$1") (pinfunction "P$1_P$1") (pintype "bidirectional"))
    )
    (net (code "2") (name "Net-(C1-Pad1)") (class "Default")
      (node (ref "C1") (pin "1") (pinfunction "1_1") (pintype "passive"))
      (node (ref "C10") (pin "1") (pinfunction "1_1") (pintype "passive"))
      (node (ref "C11") (pin "1") (pinfunction "1_1") (pintype "passive"))
      (node (ref "C12") (pin "1") (pinfunction "1_1") (pintype "passive"))
      (node (ref "C13") (pin "1") (pinfunction "1_1") (pintype "passive"))
      (node (ref "C14") (pin "1") (pinfunction "1_1") (pintype "passive"))
      (node (ref "C15") (pin "1") (pinfunction "1_1") (pintype "passive"))
      (node (ref "C17") (pin "1") (pinfunction "1_1") (pintype "passive"))
      (node (ref "C18") (pin "1") (pinfunction "1_1") (pintype "passive"))
      (node (ref "C19") (pin "1") (pinfunction "1_1") (pintype "passive"))
      (node (ref "C2") (pin "1") (pinfunction "1_1") (pintype "passive"))
      (node (ref "C20") (pin "1") (pinfunction "1_1") (pintype "passive"))
      (node (ref "C21") (pin "1") (pinfunction "1_1") (pintype "passive"))
      (node (ref "C22") (pin "1") (pinfunction "1_1") (pintype "passive"))
      (node (ref "C23") (pin "1") (pinfunction "1_1") (pintype "passive"))
      (node (ref "C25") (pin "1") (pinfunction "1_1") (pintype "passive"))
      (node (ref "C26") (pin "1") (pinfunction "1_1") (pintype "passive"))
      (node (ref "C27") (pin "1") (pinfunction "1_1") (pintype "passive"))
      (node (ref "C28") (pin "1") (pinfunction "1_1") (pintype "passive"))
      (node (ref "C29") (pin "1") (pinfunction "1_1") (pintype "passive"))
      (node (ref "C3") (pin "1") (pinfunction "1_1") (pintype "passive"))
      (node (ref "C30") (pin "1") (pinfunction "1_1") (pintype "passive"))
      (node (ref "C31") (pin "1") (pinfunction "1_1") (pintype "passive"))
      (node (ref "C33") (pin "1") (pinfunction "1_1") (pintype "passive"))
      (node (ref "C34") (pin "1") (pinfunction "1_1") (pintype "passive"))
      (node (ref "C35") (pin "1") (pinfunction "1_1") (pintype "passive"))
      (node (ref "C36") (pin "1") (pinfunction "1_1") (pintype "passive"))
      (node (ref "C37") (pin "1") (pinfunction "1_1") (pintype "passive"))
      (node (ref "C38") (pin "1") (pinfunction "1_1") (pintype "passive"))
      (node (ref "C39") (pin "1") (pinfunction "1_1") (pintype "passive"))
      (node (ref "C4") (pin "1") (pinfunction "1_1") (pintype "passive"))
      (node (ref "C41") (pin "1") (pinfunction "1_1") (pintype "passive"))
      (node (ref "C42") (pin "1") (pinfunction "1_1") (pintype "passive"))
      (node (ref "C43") (pin "1") (pinfunction "1_1") (pintype "passive"))
      (node (ref "C44") (pin "1") (pinfunction "1_1") (pintype "passive"))
      (node (ref "C45") (pin "1") (pinfunction "1_1") (pintype "passive"))
      (node (ref "C46") (pin "1") (pinfunction "1_1") (pintype "passive"))
      (node (ref "C47") (pin "1") (pinfunction "1_1") (pintype "passive"))
      (node (ref "C49") (pin "1") (pinfunction "1_1") (pintype "passive"))
      (node (ref "C5") (pin "1") (pinfunction "1_1") (pintype "passive"))
      (node (ref "C50") (pin "1") (pinfunction "1_1") (pintype "passive"))
      (node (ref "C51") (pin "1") (pinfunction "1_1") (pintype "passive"))
      (node (ref "C52") (pin "1") (pinfunction "1_1") (pintype "passive"))
      (node (ref "C53") (pin "1") (pinfunction "1_1") (pintype "passive"))
      (node (ref "C54") (pin "1") (pinfunction "1_1") (pintype "passive"))
      (node (ref "C55") (pin "1") (pinfunction "1_1") (pintype "passive"))
      (node (ref "C57") (pin "1") (pinfunction "1_1") (pintype "passive"))
      (node (ref "C58") (pin "1") (pinfunction "1_1") (pintype "passive"))
      (node (ref "C59") (pin "1") (pinfunction "1_1") (pintype "passive"))
      (node (ref "C6") (pin "1") (pinfunction "1_1") (pintype "passive"))
      (node (ref "C60") (pin "1") (pinfunction "1_1") (pintype "passive"))
      (node (ref "C61") (pin "1") (pinfunction "1_1") (pintype "passive"))
      (node (ref "C62") (pin "1") (pinfunction "1_1") (pintype "passive"))
      (node (ref "C63") (pin "1") (pinfunction "1_1") (pintype "passive"))
      (node (ref "C7") (pin "1") (pinfunction "1_1") (pintype "passive"))
      (node (ref "C9") (pin "1") (pinfunction "1_1") (pintype "passive"))
      (node (ref "JP1") (pin "2") (pinfunction "2_2") (pintype "passive"))
      (node (ref "JP2") (pin "2") (pinfunction "2_2") (pintype "passive"))
      (node (ref "LED1") (pin "LEDVDD") (pinfunction "LEDVDD_LEDVDD") (pintype "power_in"))
      (node (ref "LED1") (pin "VDD") (pinfunction "VDD_VDD") (pintype "power_in"))
      (node (ref "LED10") (pin "LEDVDD") (pinfunction "LEDVDD_LEDVDD") (pintype "power_in"))
      (node (ref "LED10") (pin "VDD") (pinfunction "VDD_VDD") (pintype "power_in"))
      (node (ref "LED11") (pin "LEDVDD") (pinfunction "LEDVDD_LEDVDD") (pintype "power_in"))
      (node (ref "LED11") (pin "VDD") (pinfunction "VDD_VDD") (pintype "power_in"))
      (node (ref "LED12") (pin "LEDVDD") (pinfunction "LEDVDD_LEDVDD") (pintype "power_in"))
      (node (ref "LED12") (pin "VDD") (pinfunction "VDD_VDD") (pintype "power_in"))
      (node (ref "LED13") (pin "LEDVDD") (pinfunction "LEDVDD_LEDVDD") (pintype "power_in"))
      (node (ref "LED13") (pin "VDD") (pinfunction "VDD_VDD") (pintype "power_in"))
      (node (ref "LED14") (pin "LEDVDD") (pinfunction "LEDVDD_LEDVDD") (pintype "power_in"))
      (node (ref "LED14") (pin "VDD") (pinfunction "VDD_VDD") (pintype "power_in"))
      (node (ref "LED15") (pin "LEDVDD") (pinfunction "LEDVDD_LEDVDD") (pintype "power_in"))
      (node (ref "LED15") (pin "VDD") (pinfunction "VDD_VDD") (pintype "power_in"))
      (node (ref "LED16") (pin "LEDVDD") (pinfunction "LEDVDD_LEDVDD") (pintype "power_in"))
      (node (ref "LED16") (pin "VDD") (pinfunction "VDD_VDD") (pintype "power_in"))
      (node (ref "LED17") (pin "LEDVDD") (pinfunction "LEDVDD_LEDVDD") (pintype "power_in"))
      (node (ref "LED17") (pin "VDD") (pinfunction "VDD_VDD") (pintype "power_in"))
      (node (ref "LED18") (pin "LEDVDD") (pinfunction "LEDVDD_LEDVDD") (pintype "power_in"))
      (node (ref "LED18") (pin "VDD") (pinfunction "VDD_VDD") (pintype "power_in"))
      (node (ref "LED19") (pin "LEDVDD") (pinfunction "LEDVDD_LEDVDD") (pintype "power_in"))
      (node (ref "LED19") (pin "VDD") (pinfunction "VDD_VDD") (pintype "power_in"))
      (node (ref "LED2") (pin "LEDVDD") (pinfunction "LEDVDD_LEDVDD") (pintype "power_in"))
      (node (ref "LED2") (pin "VDD") (pinfunction "VDD_VDD") (pintype "power_in"))
      (node (ref "LED20") (pin "LEDVDD") (pinfunction "LEDVDD_LEDVDD") (pintype "power_in"))
      (node (ref "LED20") (pin "VDD") (pinfunction "VDD_VDD") (pintype "power_in"))
      (node (ref "LED21") (pin "LEDVDD") (pinfunction "LEDVDD_LEDVDD") (pintype "power_in"))
      (node (ref "LED21") (pin "VDD") (pinfunction "VDD_VDD") (pintype "power_in"))
      (node (ref "LED22") (pin "LEDVDD") (pinfunction "LEDVDD_LEDVDD") (pintype "power_in"))
      (node (ref "LED22") (pin "VDD") (pinfunction "VDD_VDD") (pintype "power_in"))
      (node (ref "LED23") (pin "LEDVDD") (pinfunction "LEDVDD_LEDVDD") (pintype "power_in"))
      (node (ref "LED23") (pin "VDD") (pinfunction "VDD_VDD") (pintype "power_in"))
      (node (ref "LED24") (pin "LEDVDD") (pinfunction "LEDVDD_LEDVDD") (pintype "power_in"))
      (node (ref "LED24") (pin "VDD") (pinfunction "VDD_VDD") (pintype "power_in"))
      (node (ref "LED25") (pin "LEDVDD") (pinfunction "LEDVDD_LEDVDD") (pintype "power_in"))
      (node (ref "LED25") (pin "VDD") (pinfunction "VDD_VDD") (pintype "power_in"))
      (node (ref "LED26") (pin "LEDVDD") (pinfunction "LEDVDD_LEDVDD") (pintype "power_in"))
      (node (ref "LED26") (pin "VDD") (pinfunction "VDD_VDD") (pintype "power_in"))
      (node (ref "LED27") (pin "LEDVDD") (pinfunction "LEDVDD_LEDVDD") (pintype "power_in"))
      (node (ref "LED27") (pin "VDD") (pinfunction "VDD_VDD") (pintype "power_in"))
      (node (ref "LED28") (pin "LEDVDD") (pinfunction "LEDVDD_LEDVDD") (pintype "power_in"))
      (node (ref "LED28") (pin "VDD") (pinfunction "VDD_VDD") (pintype "power_in"))
      (node (ref "LED29") (pin "LEDVDD") (pinfunction "LEDVDD_LEDVDD") (pintype "power_in"))
      (node (ref "LED29") (pin "VDD") (pinfunction "VDD_VDD") (pintype "power_in"))
      (node (ref "LED3") (pin "LEDVDD") (pinfunction "LEDVDD_LEDVDD") (pintype "power_in"))
      (node (ref "LED3") (pin "VDD") (pinfunction "VDD_VDD") (pintype "power_in"))
      (node (ref "LED30") (pin "LEDVDD") (pinfunction "LEDVDD_LEDVDD") (pintype "power_in"))
      (node (ref "LED30") (pin "VDD") (pinfunction "VDD_VDD") (pintype "power_in"))
      (node (ref "LED31") (pin "LEDVDD") (pinfunction "LEDVDD_LEDVDD") (pintype "power_in"))
      (node (ref "LED31") (pin "VDD") (pinfunction "VDD_VDD") (pintype "power_in"))
      (node (ref "LED32") (pin "LEDVDD") (pinfunction "LEDVDD_LEDVDD") (pintype "power_in"))
      (node (ref "LED32") (pin "VDD") (pinfunction "VDD_VDD") (pintype "power_in"))
      (node (ref "LED33") (pin "LEDVDD") (pinfunction "LEDVDD_LEDVDD") (pintype "power_in"))
      (node (ref "LED33") (pin "VDD") (pinfunction "VDD_VDD") (pintype "power_in"))
      (node (ref "LED34") (pin "LEDVDD") (pinfunction "LEDVDD_LEDVDD") (pintype "power_in"))
      (node (ref "LED34") (pin "VDD") (pinfunction "VDD_VDD") (pintype "power_in"))
      (node (ref "LED35") (pin "LEDVDD") (pinfunction "LEDVDD_LEDVDD") (pintype "power_in"))
      (node (ref "LED35") (pin "VDD") (pinfunction "VDD_VDD") (pintype "power_in"))
      (node (ref "LED36") (pin "LEDVDD") (pinfunction "LEDVDD_LEDVDD") (pintype "power_in"))
      (node (ref "LED36") (pin "VDD") (pinfunction "VDD_VDD") (pintype "power_in"))
      (node (ref "LED37") (pin "LEDVDD") (pinfunction "LEDVDD_LEDVDD") (pintype "power_in"))
      (node (ref "LED37") (pin "VDD") (pinfunction "VDD_VDD") (pintype "power_in"))
      (node (ref "LED38") (pin "LEDVDD") (pinfunction "LEDVDD_LEDVDD") (pintype "power_in"))
      (node (ref "LED38") (pin "VDD") (pinfunction "VDD_VDD") (pintype "power_in"))
      (node (ref "LED39") (pin "LEDVDD") (pinfunction "LEDVDD_LEDVDD") (pintype "power_in"))
      (node (ref "LED39") (pin "VDD") (pinfunction "VDD_VDD") (pintype "power_in"))
      (node (ref "LED4") (pin "LEDVDD") (pinfunction "LEDVDD_LEDVDD") (pintype "power_in"))
      (node (ref "LED4") (pin "VDD") (pinfunction "VDD_VDD") (pintype "power_in"))
      (node (ref "LED40") (pin "LEDVDD") (pinfunction "LEDVDD_LEDVDD") (pintype "power_in"))
      (node (ref "LED40") (pin "VDD") (pinfunction "VDD_VDD") (pintype "power_in"))
      (node (ref "LED41") (pin "LEDVDD") (pinfunction "LEDVDD_LEDVDD") (pintype "power_in"))
      (node (ref "LED41") (pin "VDD") (pinfunction "VDD_VDD") (pintype "power_in"))
      (node (ref "LED42") (pin "LEDVDD") (pinfunction "LEDVDD_LEDVDD") (pintype "power_in"))
      (node (ref "LED42") (pin "VDD") (pinfunction "VDD_VDD") (pintype "power_in"))
      (node (ref "LED43") (pin "LEDVDD") (pinfunction "LEDVDD_LEDVDD") (pintype "power_in"))
      (node (ref "LED43") (pin "VDD") (pinfunction "VDD_VDD") (pintype "power_in"))
      (node (ref "LED44") (pin "LEDVDD") (pinfunction "LEDVDD_LEDVDD") (pintype "power_in"))
      (node (ref "LED44") (pin "VDD") (pinfunction "VDD_VDD") (pintype "power_in"))
      (node (ref "LED45") (pin "LEDVDD") (pinfunction "LEDVDD_LEDVDD") (pintype "power_in"))
      (node (ref "LED45") (pin "VDD") (pinfunction "VDD_VDD") (pintype "power_in"))
      (node (ref "LED46") (pin "LEDVDD") (pinfunction "LEDVDD_LEDVDD") (pintype "power_in"))
      (node (ref "LED46") (pin "VDD") (pinfunction "VDD_VDD") (pintype "power_in"))
      (node (ref "LED47") (pin "LEDVDD") (pinfunction "LEDVDD_LEDVDD") (pintype "power_in"))
      (node (ref "LED47") (pin "VDD") (pinfunction "VDD_VDD") (pintype "power_in"))
      (node (ref "LED48") (pin "LEDVDD") (pinfunction "LEDVDD_LEDVDD") (pintype "power_in"))
      (node (ref "LED48") (pin "VDD") (pinfunction "VDD_VDD") (pintype "power_in"))
      (node (ref "LED49") (pin "LEDVDD") (pinfunction "LEDVDD_LEDVDD") (pintype "power_in"))
      (node (ref "LED49") (pin "VDD") (pinfunction "VDD_VDD") (pintype "power_in"))
      (node (ref "LED5") (pin "LEDVDD") (pinfunction "LEDVDD_LEDVDD") (pintype "power_in"))
      (node (ref "LED5") (pin "VDD") (pinfunction "VDD_VDD") (pintype "power_in"))
      (node (ref "LED50") (pin "LEDVDD") (pinfunction "LEDVDD_LEDVDD") (pintype "power_in"))
      (node (ref "LED50") (pin "VDD") (pinfunction "VDD_VDD") (pintype "power_in"))
      (node (ref "LED51") (pin "LEDVDD") (pinfunction "LEDVDD_LEDVDD") (pintype "power_in"))
      (node (ref "LED51") (pin "VDD") (pinfunction "VDD_VDD") (pintype "power_in"))
      (node (ref "LED52") (pin "LEDVDD") (pinfunction "LEDVDD_LEDVDD") (pintype "power_in"))
      (node (ref "LED52") (pin "VDD") (pinfunction "VDD_VDD") (pintype "power_in"))
      (node (ref "LED53") (pin "LEDVDD") (pinfunction "LEDVDD_LEDVDD") (pintype "power_in"))
      (node (ref "LED53") (pin "VDD") (pinfunction "VDD_VDD") (pintype "power_in"))
      (node (ref "LED54") (pin "LEDVDD") (pinfunction "LEDVDD_LEDVDD") (pintype "power_in"))
      (node (ref "LED54") (pin "VDD") (pinfunction "VDD_VDD") (pintype "power_in"))
      (node (ref "LED55") (pin "LEDVDD") (pinfunction "LEDVDD_LEDVDD") (pintype "power_in"))
      (node (ref "LED55") (pin "VDD") (pinfunction "VDD_VDD") (pintype "power_in"))
      (node (ref "LED56") (pin "LEDVDD") (pinfunction "LEDVDD_LEDVDD") (pintype "power_in"))
      (node (ref "LED56") (pin "VDD") (pinfunction "VDD_VDD") (pintype "power_in"))
      (node (ref "LED57") (pin "LEDVDD") (pinfunction "LEDVDD_LEDVDD") (pintype "power_in"))
      (node (ref "LED57") (pin "VDD") (pinfunction "VDD_VDD") (pintype "power_in"))
      (node (ref "LED58") (pin "LEDVDD") (pinfunction "LEDVDD_LEDVDD") (pintype "power_in"))
      (node (ref "LED58") (pin "VDD") (pinfunction "VDD_VDD") (pintype "power_in"))
      (node (ref "LED59") (pin "LEDVDD") (pinfunction "LEDVDD_LEDVDD") (pintype "power_in"))
      (node (ref "LED59") (pin "VDD") (pinfunction "VDD_VDD") (pintype "power_in"))
      (node (ref "LED6") (pin "LEDVDD") (pinfunction "LEDVDD_LEDVDD") (pintype "power_in"))
      (node (ref "LED6") (pin "VDD") (pinfunction "VDD_VDD") (pintype "power_in"))
      (node (ref "LED60") (pin "LEDVDD") (pinfunction "LEDVDD_LEDVDD") (pintype "power_in"))
      (node (ref "LED60") (pin "VDD") (pinfunction "VDD_VDD") (pintype "power_in"))
      (node (ref "LED61") (pin "LEDVDD") (pinfunction "LEDVDD_LEDVDD") (pintype "power_in"))
      (node (ref "LED61") (pin "VDD") (pinfunction "VDD_VDD") (pintype "power_in"))
      (node (ref "LED62") (pin "LEDVDD") (pinfunction "LEDVDD_LEDVDD") (pintype "power_in"))
      (node (ref "LED62") (pin "VDD") (pinfunction "VDD_VDD") (pintype "power_in"))
      (node (ref "LED63") (pin "LEDVDD") (pinfunction "LEDVDD_LEDVDD") (pintype "power_in"))
      (node (ref "LED63") (pin "VDD") (pinfunction "VDD_VDD") (pintype "power_in"))
      (node (ref "LED64") (pin "LEDVDD") (pinfunction "LEDVDD_LEDVDD") (pintype "power_in"))
      (node (ref "LED64") (pin "VDD") (pinfunction "VDD_VDD") (pintype "power_in"))
      (node (ref "LED7") (pin "LEDVDD") (pinfunction "LEDVDD_LEDVDD") (pintype "power_in"))
      (node (ref "LED7") (pin "VDD") (pinfunction "VDD_VDD") (pintype "power_in"))
      (node (ref "LED8") (pin "LEDVDD") (pinfunction "LEDVDD_LEDVDD") (pintype "power_in"))
      (node (ref "LED8") (pin "VDD") (pinfunction "VDD_VDD") (pintype "power_in"))
      (node (ref "LED9") (pin "LEDVDD") (pinfunction "LEDVDD_LEDVDD") (pintype "power_in"))
      (node (ref "LED9") (pin "VDD") (pinfunction "VDD_VDD") (pintype "power_in"))
    )
    (net (code "3") (name "Net-(JP1-Pad1)") (class "Default")
      (node (ref "JP1") (pin "1") (pinfunction "1_1") (pintype "passive"))
      (node (ref "LED1") (pin "DI") (pinfunction "DI_DI") (pintype "input"))
    )
    (net (code "4") (name "Net-(JP2-Pad1)") (class "Default")
      (node (ref "JP2") (pin "1") (pinfunction "1_1") (pintype "passive"))
      (node (ref "LED64") (pin "DO") (pinfunction "DO_DO") (pintype "output"))
    )
    (net (code "5") (name "Net-(LED1-PadDO)") (class "Default")
      (node (ref "LED1") (pin "DO") (pinfunction "DO_DO") (pintype "output"))
      (node (ref "LED2") (pin "DI") (pinfunction "DI_DI") (pintype "input"))
    )
    (net (code "6") (name "Net-(LED2-PadDO)") (class "Default")
      (node (ref "LED2") (pin "DO") (pinfunction "DO_DO") (pintype "output"))
      (node (ref "LED3") (pin "DI") (pinfunction "DI_DI") (pintype "input"))
    )
    (net (code "7") (name "Net-(LED3-PadDO)") (class "Default")
      (node (ref "LED3") (pin "DO") (pinfunction "DO_DO") (pintype "output"))
      (node (ref "LED4") (pin "DI") (pinfunction "DI_DI") (pintype "input"))
    )
    (net (code "8") (name "Net-(LED4-PadDO)") (class "Default")
      (node (ref "LED4") (pin "DO") (pinfunction "DO_DO") (pintype "output"))
      (node (ref "LED5") (pin "DI") (pinfunction "DI_DI") (pintype "input"))
    )
    (net (code "9") (name "Net-(LED5-PadDO)") (class "Default")
      (node (ref "LED5") (pin "DO") (pinfunction "DO_DO") (pintype "output"))
      (node (ref "LED6") (pin "DI") (pinfunction "DI_DI") (pintype "input"))
    )
    (net (code "10") (name "Net-(LED6-PadDO)") (class "Default")
      (node (ref "LED6") (pin "DO") (pinfunction "DO_DO") (pintype "output"))
      (node (ref "LED7") (pin "DI") (pinfunction "DI_DI") (pintype "input"))
    )
    (net (code "11") (name "Net-(LED7-PadDO)") (class "Default")
      (node (ref "LED7") (pin "DO") (pinfunction "DO_DO") (pintype "output"))
      (node (ref "LED8") (pin "DI") (pinfunction "DI_DI") (pintype "input"))
    )
    (net (code "12") (name "Net-(LED8-PadDO)") (class "Default")
      (node (ref "LED8") (pin "DO") (pinfunction "DO_DO") (pintype "output"))
      (node (ref "LED9") (pin "DI") (pinfunction "DI_DI") (pintype "input"))
    )
    (net (code "13") (name "Net-(LED10-PadDI)") (class "Default")
      (node (ref "LED10") (pin "DI") (pinfunction "DI_DI") (pintype "input"))
      (node (ref "LED9") (pin "DO") (pinfunction "DO_DO") (pintype "output"))
    )
    (net (code "14") (name "Net-(LED10-PadDO)") (class "Default")
      (node (ref "LED10") (pin "DO") (pinfunction "DO_DO") (pintype "output"))
      (node (ref "LED11") (pin "DI") (pinfunction "DI_DI") (pintype "input"))
    )
    (net (code "15") (name "Net-(LED11-PadDO)") (class "Default")
      (node (ref "LED11") (pin "DO") (pinfunction "DO_DO") (pintype "output"))
      (node (ref "LED12") (pin "DI") (pinfunction "DI_DI") (pintype "input"))
    )
    (net (code "16") (name "Net-(LED12-PadDO)") (class "Default")
      (node (ref "LED12") (pin "DO") (pinfunction "DO_DO") (pintype "output"))
      (node (ref "LED13") (pin "DI") (pinfunction "DI_DI") (pintype "input"))
    )
    (net (code "17") (name "Net-(LED13-PadDO)") (class "Default")
      (node (ref "LED13") (pin "DO") (pinfunction "DO_DO") (pintype "output"))
      (node (ref "LED14") (pin "DI") (pinfunction "DI_DI") (pintype "input"))
    )
    (net (code "18") (name "Net-(LED14-PadDO)") (class "Default")
      (node (ref "LED14") (pin "DO") (pinfunction "DO_DO") (pintype "output"))
      (node (ref "LED15") (pin "DI") (pinfunction "DI_DI") (pintype "input"))
    )
    (net (code "19") (name "Net-(LED15-PadDO)") (class "Default")
      (node (ref "LED15") (pin "DO") (pinfunction "DO_DO") (pintype "output"))
      (node (ref "LED16") (pin "DI") (pinfunction "DI_DI") (pintype "input"))
    )
    (net (code "20") (name "Net-(LED16-PadDO)") (class "Default")
      (node (ref "LED16") (pin "DO") (pinfunction "DO_DO") (pintype "output"))
      (node (ref "LED17") (pin "DI") (pinfunction "DI_DI") (pintype "input"))
    )
    (net (code "21") (name "Net-(LED17-PadDO)") (class "Default")
      (node (ref "LED17") (pin "DO") (pinfunction "DO_DO") (pintype "output"))
      (node (ref "LED18") (pin "DI") (pinfunction "DI_DI") (pintype "input"))
    )
    (net (code "22") (name "Net-(LED18-PadDO)") (class "Default")
      (node (ref "LED18") (pin "DO") (pinfunction "DO_DO") (pintype "output"))
      (node (ref "LED19") (pin "DI") (pinfunction "DI_DI") (pintype "input"))
    )
    (net (code "23") (name "Net-(LED19-PadDO)") (class "Default")
      (node (ref "LED19") (pin "DO") (pinfunction "DO_DO") (pintype "output"))
      (node (ref "LED20") (pin "DI") (pinfunction "DI_DI") (pintype "input"))
    )
    (net (code "24") (name "Net-(LED20-PadDO)") (class "Default")
      (node (ref "LED20") (pin "DO") (pinfunction "DO_DO") (pintype "output"))
      (node (ref "LED21") (pin "DI") (pinfunction "DI_DI") (pintype "input"))
    )
    (net (code "25") (name "Net-(LED21-PadDO)") (class "Default")
      (node (ref "LED21") (pin "DO") (pinfunction "DO_DO") (pintype "output"))
      (node (ref "LED22") (pin "DI") (pinfunction "DI_DI") (pintype "input"))
    )
    (net (code "26") (name "Net-(LED22-PadDO)") (class "Default")
      (node (ref "LED22") (pin "DO") (pinfunction "DO_DO") (pintype "output"))
      (node (ref "LED23") (pin "DI") (pinfunction "DI_DI") (pintype "input"))
    )
    (net (code "27") (name "Net-(LED23-PadDO)") (class "Default")
      (node (ref "LED23") (pin "DO") (pinfunction "DO_DO") (pintype "output"))
      (node (ref "LED24") (pin "DI") (pinfunction "DI_DI") (pintype "input"))
    )
    (net (code "28") (name "Net-(LED24-PadDO)") (class "Default")
      (node (ref "LED24") (pin "DO") (pinfunction "DO_DO") (pintype "output"))
      (node (ref "LED25") (pin "DI") (pinfunction "DI_DI") (pintype "input"))
    )
    (net (code "29") (name "Net-(LED25-PadDO)") (class "Default")
      (node (ref "LED25") (pin "DO") (pinfunction "DO_DO") (pintype "output"))
      (node (ref "LED26") (pin "DI") (pinfunction "DI_DI") (pintype "input"))
    )
    (net (code "30") (name "Net-(LED26-PadDO)") (class "Default")
      (node (ref "LED26") (pin "DO") (pinfunction "DO_DO") (pintype "output"))
      (node (ref "LED27") (pin "DI") (pinfunction "DI_DI") (pintype "input"))
    )
    (net (code "31") (name "Net-(LED27-PadDO)") (class "Default")
      (node (ref "LED27") (pin "DO") (pinfunction "DO_DO") (pintype "output"))
      (node (ref "LED28") (pin "DI") (pinfunction "DI_DI") (pintype "input"))
    )
    (net (code "32") (name "Net-(LED28-PadDO)") (class "Default")
      (node (ref "LED28") (pin "DO") (pinfunction "DO_DO") (pintype "output"))
      (node (ref "LED29") (pin "DI") (pinfunction "DI_DI") (pintype "input"))
    )
    (net (code "33") (name "Net-(LED29-PadDO)") (class "Default")
      (node (ref "LED29") (pin "DO") (pinfunction "DO_DO") (pintype "output"))
      (node (ref "LED30") (pin "DI") (pinfunction "DI_DI") (pintype "input"))
    )
    (net (code "34") (name "Net-(LED30-PadDO)") (class "Default")
      (node (ref "LED30") (pin "DO") (pinfunction "DO_DO") (pintype "output"))
      (node (ref "LED31") (pin "DI") (pinfunction "DI_DI") (pintype "input"))
    )
    (net (code "35") (name "Net-(LED31-PadDO)") (class "Default")
      (node (ref "LED31") (pin "DO") (pinfunction "DO_DO") (pintype "output"))
      (node (ref "LED32") (pin "DI") (pinfunction "DI_DI") (pintype "input"))
    )
    (net (code "36") (name "Net-(LED32-PadDO)") (class "Default")
      (node (ref "LED32") (pin "DO") (pinfunction "DO_DO") (pintype "output"))
      (node (ref "LED33") (pin "DI") (pinfunction "DI_DI") (pintype "input"))
    )
    (net (code "37") (name "Net-(LED33-PadDO)") (class "Default")
      (node (ref "LED33") (pin "DO") (pinfunction "DO_DO") (pintype "output"))
      (node (ref "LED34") (pin "DI") (pinfunction "DI_DI") (pintype "input"))
    )
    (net (code "38") (name "Net-(LED34-PadDO)") (class "Default")
      (node (ref "LED34") (pin "DO") (pinfunction "DO_DO") (pintype "output"))
      (node (ref "LED35") (pin "DI") (pinfunction "DI_DI") (pintype "input"))
    )
    (net (code "39") (name "Net-(LED35-PadDO)") (class "Default")
      (node (ref "LED35") (pin "DO") (pinfunction "DO_DO") (pintype "output"))
      (node (ref "LED36") (pin "DI") (pinfunction "DI_DI") (pintype "input"))
    )
    (net (code "40") (name "Net-(LED36-PadDO)") (class "Default")
      (node (ref "LED36") (pin "DO") (pinfunction "DO_DO") (pintype "output"))
      (node (ref "LED37") (pin "DI") (pinfunction "DI_DI") (pintype "input"))
    )
    (net (code "41") (name "Net-(LED37-PadDO)") (class "Default")
      (node (ref "LED37") (pin "DO") (pinfunction "DO_DO") (pintype "output"))
      (node (ref "LED38") (pin "DI") (pinfunction "DI_DI") (pintype "input"))
    )
    (net (code "42") (name "Net-(LED38-PadDO)") (class "Default")
      (node (ref "LED38") (pin "DO") (pinfunction "DO_DO") (pintype "output"))
      (node (ref "LED39") (pin "DI") (pinfunction "DI_DI") (pintype "input"))
    )
    (net (code "43") (name "Net-(LED39-PadDO)") (class "Default")
      (node (ref "LED39") (pin "DO") (pinfunction "DO_DO") (pintype "output"))
      (node (ref "LED40") (pin "DI") (pinfunction "DI_DI") (pintype "input"))
    )
    (net (code "44") (name "Net-(LED40-PadDO)") (class "Default")
      (node (ref "LED40") (pin "DO") (pinfunction "DO_DO") (pintype "output"))
      (node (ref "LED41") (pin "DI") (pinfunction "DI_DI") (pintype "input"))
    )
    (net (code "45") (name "Net-(LED41-PadDO)") (class "Default")
      (node (ref "LED41") (pin "DO") (pinfunction "DO_DO") (pintype "output"))
      (node (ref "LED42") (pin "DI") (pinfunction "DI_DI") (pintype "input"))
    )
    (net (code "46") (name "Net-(LED42-PadDO)") (class "Default")
      (node (ref "LED42") (pin "DO") (pinfunction "DO_DO") (pintype "output"))
      (node (ref "LED43") (pin "DI") (pinfunction "DI_DI") (pintype "input"))
    )
    (net (code "47") (name "Net-(LED43-PadDO)") (class "Default")
      (node (ref "LED43") (pin "DO") (pinfunction "DO_DO") (pintype "output"))
      (node (ref "LED44") (pin "DI") (pinfunction "DI_DI") (pintype "input"))
    )
    (net (code "48") (name "Net-(LED44-PadDO)") (class "Default")
      (node (ref "LED44") (pin "DO") (pinfunction "DO_DO") (pintype "output"))
      (node (ref "LED45") (pin "DI") (pinfunction "DI_DI") (pintype "input"))
    )
    (net (code "49") (name "Net-(LED45-PadDO)") (class "Default")
      (node (ref "LED45") (pin "DO") (pinfunction "DO_DO") (pintype "output"))
      (node (ref "LED46") (pin "DI") (pinfunction "DI_DI") (pintype "input"))
    )
    (net (code "50") (name "Net-(LED46-PadDO)") (class "Default")
      (node (ref "LED46") (pin "DO") (pinfunction "DO_DO") (pintype "output"))
      (node (ref "LED47") (pin "DI") (pinfunction "DI_DI") (pintype "input"))
    )
    (net (code "51") (name "Net-(LED47-PadDO)") (class "Default")
      (node (ref "LED47") (pin "DO") (pinfunction "DO_DO") (pintype "output"))
      (node (ref "LED48") (pin "DI") (pinfunction "DI_DI") (pintype "input"))
    )
    (net (code "52") (name "Net-(LED48-PadDO)") (class "Default")
      (node (ref "LED48") (pin "DO") (pinfunction "DO_DO") (pintype "output"))
      (node (ref "LED49") (pin "DI") (pinfunction "DI_DI") (pintype "input"))
    )
    (net (code "53") (name "Net-(LED49-PadDO)") (class "Default")
      (node (ref "LED49") (pin "DO") (pinfunction "DO_DO") (pintype "output"))
      (node (ref "LED50") (pin "DI") (pinfunction "DI_DI") (pintype "input"))
    )
    (net (code "54") (name "Net-(LED50-PadDO)") (class "Default")
      (node (ref "LED50") (pin "DO") (pinfunction "DO_DO") (pintype "output"))
      (node (ref "LED51") (pin "DI") (pinfunction "DI_DI") (pintype "input"))
    )
    (net (code "55") (name "Net-(LED51-PadDO)") (class "Default")
      (node (ref "LED51") (pin "DO") (pinfunction "DO_DO") (pintype "output"))
      (node (ref "LED52") (pin "DI") (pinfunction "DI_DI") (pintype "input"))
    )
    (net (code "56") (name "Net-(LED52-PadDO)") (class "Default")
      (node (ref "LED52") (pin "DO") (pinfunction "DO_DO") (pintype "output"))
      (node (ref "LED53") (pin "DI") (pinfunction "DI_DI") (pintype "input"))
    )
    (net (code "57") (name "Net-(LED53-PadDO)") (class "Default")
      (node (ref "LED53") (pin "DO") (pinfunction "DO_DO") (pintype "output"))
      (node (ref "LED54") (pin "DI") (pinfunction "DI_DI") (pintype "input"))
    )
    (net (code "58") (name "Net-(LED54-PadDO)") (class "Default")
      (node (ref "LED54") (pin "DO") (pinfunction "DO_DO") (pintype "output"))
      (node (ref "LED55") (pin "DI") (pinfunction "DI_DI") (pintype "input"))
    )
    (net (code "59") (name "Net-(LED55-PadDO)") (class "Default")
      (node (ref "LED55") (pin "DO") (pinfunction "DO_DO") (pintype "output"))
      (node (ref "LED56") (pin "DI") (pinfunction "DI_DI") (pintype "input"))
    )
    (net (code "60") (name "Net-(LED56-PadDO)") (class "Default")
      (node (ref "LED56") (pin "DO") (pinfunction "DO_DO") (pintype "output"))
      (node (ref "LED57") (pin "DI") (pinfunction "DI_DI") (pintype "input"))
    )
    (net (code "61") (name "Net-(LED57-PadDO)") (class "Default")
      (node (ref "LED57") (pin "DO") (pinfunction "DO_DO") (pintype "output"))
      (node (ref "LED58") (pin "DI") (pinfunction "DI_DI") (pintype "input"))
    )
    (net (code "62") (name "Net-(LED58-PadDO)") (class "Default")
      (node (ref "LED58") (pin "DO") (pinfunction "DO_DO") (pintype "output"))
      (node (ref "LED59") (pin "DI") (pinfunction "DI_DI") (pintype "input"))
    )
    (net (code "63") (name "Net-(LED59-PadDO)") (class "Default")
      (node (ref "LED59") (pin "DO") (pinfunction "DO_DO") (pintype "output"))
      (node (ref "LED60") (pin "DI") (pinfunction "DI_DI") (pintype "input"))
    )
    (net (code "64") (name "Net-(LED60-PadDO)") (class "Default")
      (node (ref "LED60") (pin "DO") (pinfunction "DO_DO") (pintype "output"))
      (node (ref "LED61") (pin "DI") (pinfunction "DI_DI") (pintype "input"))
    )
    (net (code "65") (name "Net-(LED61-PadDO)") (class "Default")
      (node (ref "LED61") (pin "DO") (pinfunction "DO_DO") (pintype "output"))
      (node (ref "LED62") (pin "DI") (pinfunction "DI_DI") (pintype "input"))
    )
    (net (code "66") (name "Net-(LED62-PadDO)") (class "Default")
      (node (ref "LED62") (pin "DO") (pinfunction "DO_DO") (pintype "output"))
      (node (ref "LED63") (pin "DI") (pinfunction "DI_DI") (pintype "input"))
    )
    (net (code "67") (name "Net-(LED63-PadDO)") (class "Default")
      (node (ref "LED63") (pin "DO") (pinfunction "DO_DO") (pintype "output"))
      (node (ref "LED64") (pin "DI") (pinfunction "DI_DI") (pintype "input"))
    )
  )
)
